# screen.net
KiCad netlist of a schematic drawn in Altium Designer
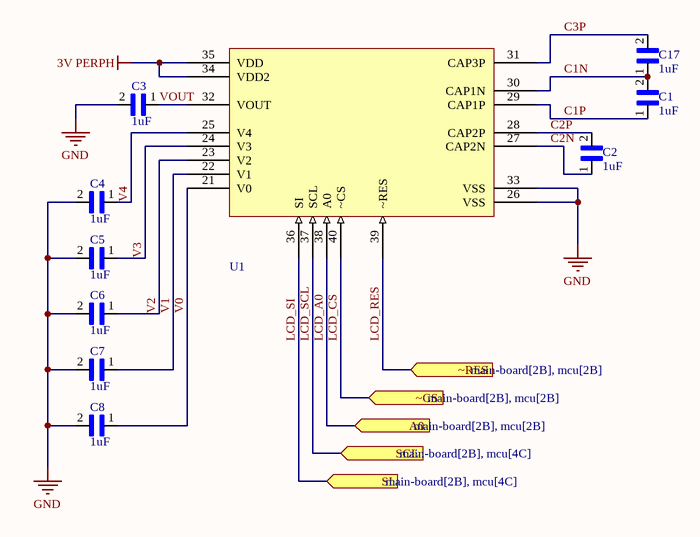
[diagram p0: screen.SchDoc]

(export (version "E")
  (design (tool "Eeschema 10.0.6"))
  (components
    (comp (ref "C1")
      (value "1uF")
      (footprint "CAPC1608X90N")
      (description "CL10B105KP8NNNC")
      (libsource (lib "") (part "CL10B105KP8NNNC_1"))
    )
    (comp (ref "C2")
      (value "1uF")
      (footprint "CAPC1608X90N")
      (description "CL10B105KP8NNNC")
      (libsource (lib "") (part "CL10B105KP8NNNC_1"))
    )
    (comp (ref "C3")
      (value "1uF")
      (footprint "CAPC1608X90N")
      (description "CL10B105KP8NNNC")
      (libsource (lib "CL10B105KP8NNNC") (part "CL10B105KP8NNNC"))
    )
    (comp (ref "C4")
      (value "1uF")
      (footprint "CAPC1608X90N")
      (description "CL10B105KP8NNNC")
      (libsource (lib "CL10B105KP8NNNC") (part "CL10B105KP8NNNC"))
    )
    (comp (ref "C5")
      (value "1uF")
      (footprint "CAPC1608X90N")
      (description "CL10B105KP8NNNC")
      (libsource (lib "CL10B105KP8NNNC") (part "CL10B105KP8NNNC"))
    )
    (comp (ref "C6")
      (value "1uF")
      (footprint "CAPC1608X90N")
      (description "CL10B105KP8NNNC")
      (libsource (lib "CL10B105KP8NNNC") (part "CL10B105KP8NNNC"))
    )
    (comp (ref "C7")
      (value "1uF")
      (footprint "CAPC1608X90N")
      (description "CL10B105KP8NNNC")
      (libsource (lib "CL10B105KP8NNNC") (part "CL10B105KP8NNNC"))
    )
    (comp (ref "C8")
      (value "1uF")
      (footprint "CAPC1608X90N")
      (description "CL10B105KP8NNNC")
      (libsource (lib "CL10B105KP8NNNC") (part "CL10B105KP8NNNC"))
    )
    (comp (ref "C17")
      (value "1uF")
      (footprint "CAPC1608X90N")
      (description "CL10B105KP8NNNC")
      (libsource (lib "") (part "CL10B105KP8NNNC_1"))
    )
    (comp (ref "U1")
      (value "INTERFACE")
      (footprint "INTERFACE")
      (libsource (lib "EADOGM132W") (part "INTERFACE"))
    )
  )
  (nets
    (net (code "1") (name "/C1N") (class "Default")
      (node (ref "C1") (pin "2") (pinfunction "2_2") (pintype "passive"))
      (node (ref "C17") (pin "1") (pinfunction "1_1") (pintype "passive"))
      (node (ref "U1") (pin "30") (pinfunction "CAP1N_30") (pintype "passive"))
    )
    (net (code "2") (name "/C1P") (class "Default")
      (node (ref "C1") (pin "1") (pinfunction "1_1") (pintype "passive"))
      (node (ref "U1") (pin "29") (pinfunction "CAP1P_29") (pintype "passive"))
    )
    (net (code "3") (name "/C2N") (class "Default")
      (node (ref "C2") (pin "1") (pinfunction "1_1") (pintype "passive"))
      (node (ref "U1") (pin "27") (pinfunction "CAP2N_27") (pintype "passive"))
    )
    (net (code "4") (name "/C2P") (class "Default")
      (node (ref "C2") (pin "2") (pinfunction "2_2") (pintype "passive"))
      (node (ref "U1") (pin "28") (pinfunction "CAP2P_28") (pintype "passive"))
    )
    (net (code "5") (name "/C3P") (class "Default")
      (node (ref "C17") (pin "2") (pinfunction "2_2") (pintype "passive"))
      (node (ref "U1") (pin "31") (pinfunction "CAP3P_31") (pintype "passive"))
    )
    (net (code "6") (name "/LCD_A0") (class "Default")
      (node (ref "U1") (pin "38") (pinfunction "A0_38") (pintype "input"))
    )
    (net (code "7") (name "/LCD_CS") (class "Default")
      (node (ref "U1") (pin "40") (pinfunction "~CS_40") (pintype "input"))
    )
    (net (code "8") (name "/LCD_RES") (class "Default")
      (node (ref "U1") (pin "39") (pinfunction "~RES_39") (pintype "input"))
    )
    (net (code "9") (name "/LCD_SCL") (class "Default")
      (node (ref "U1") (pin "37") (pinfunction "SCL_37") (pintype "input"))
    )
    (net (code "10") (name "/LCD_SI") (class "Default")
      (node (ref "U1") (pin "36") (pinfunction "SI_36") (pintype "input"))
    )
    (net (code "11") (name "/V0") (class "Default")
      (node (ref "C8") (pin "1") (pinfunction "1_1") (pintype "passive"))
      (node (ref "U1") (pin "21") (pinfunction "V0_21") (pintype "power_in"))
    )
    (net (code "12") (name "/V1") (class "Default")
      (node (ref "C7") (pin "1") (pinfunction "1_1") (pintype "passive"))
      (node (ref "U1") (pin "22") (pinfunction "V1_22") (pintype "power_in"))
    )
    (net (code "13") (name "/V2") (class "Default")
      (node (ref "C6") (pin "1") (pinfunction "1_1") (pintype "passive"))
      (node (ref "U1") (pin "23") (pinfunction "V2_23") (pintype "power_in"))
    )
    (net (code "14") (name "/V3") (class "Default")
      (node (ref "C5") (pin "1") (pinfunction "1_1") (pintype "passive"))
      (node (ref "U1") (pin "24") (pinfunction "V3_24") (pintype "power_in"))
    )
    (net (code "15") (name "/V4") (class "Default")
      (node (ref "C4") (pin "1") (pinfunction "1_1") (pintype "passive"))
      (node (ref "U1") (pin "25") (pinfunction "V4_25") (pintype "power_in"))
    )
    (net (code "16") (name "/VOUT") (class "Default")
      (node (ref "C3") (pin "1") (pinfunction "1_1") (pintype "passive"))
      (node (ref "U1") (pin "32") (pinfunction "VOUT_32") (pintype "power_in"))
    )
    (net (code "17") (name "3V PERPH") (class "Default")
      (node (ref "U1") (pin "34") (pinfunction "VDD2_34") (pintype "power_in"))
      (node (ref "U1") (pin "35") (pinfunction "VDD_35") (pintype "power_in"))
    )
    (net (code "18") (name "GND") (class "Default")
      (node (ref "C3") (pin "2") (pinfunction "2_2") (pintype "passive"))
      (node (ref "C4") (pin "2") (pinfunction "2_2") (pintype "passive"))
      (node (ref "C5") (pin "2") (pinfunction "2_2") (pintype "passive"))
      (node (ref "C6") (pin "2") (pinfunction "2_2") (pintype "passive"))
      (node (ref "C7") (pin "2") (pinfunction "2_2") (pintype "passive"))
      (node (ref "C8") (pin "2") (pinfunction "2_2") (pintype "passive"))
      (node (ref "U1") (pin "26") (pinfunction "VSS_26") (pintype "power_in"))
      (node (ref "U1") (pin "33") (pinfunction "VSS_33") (pintype "power_in"))
    )
  )
)
